# HSHV4-student_version.net
KiCad netlist of a schematic drawn in EAGLE
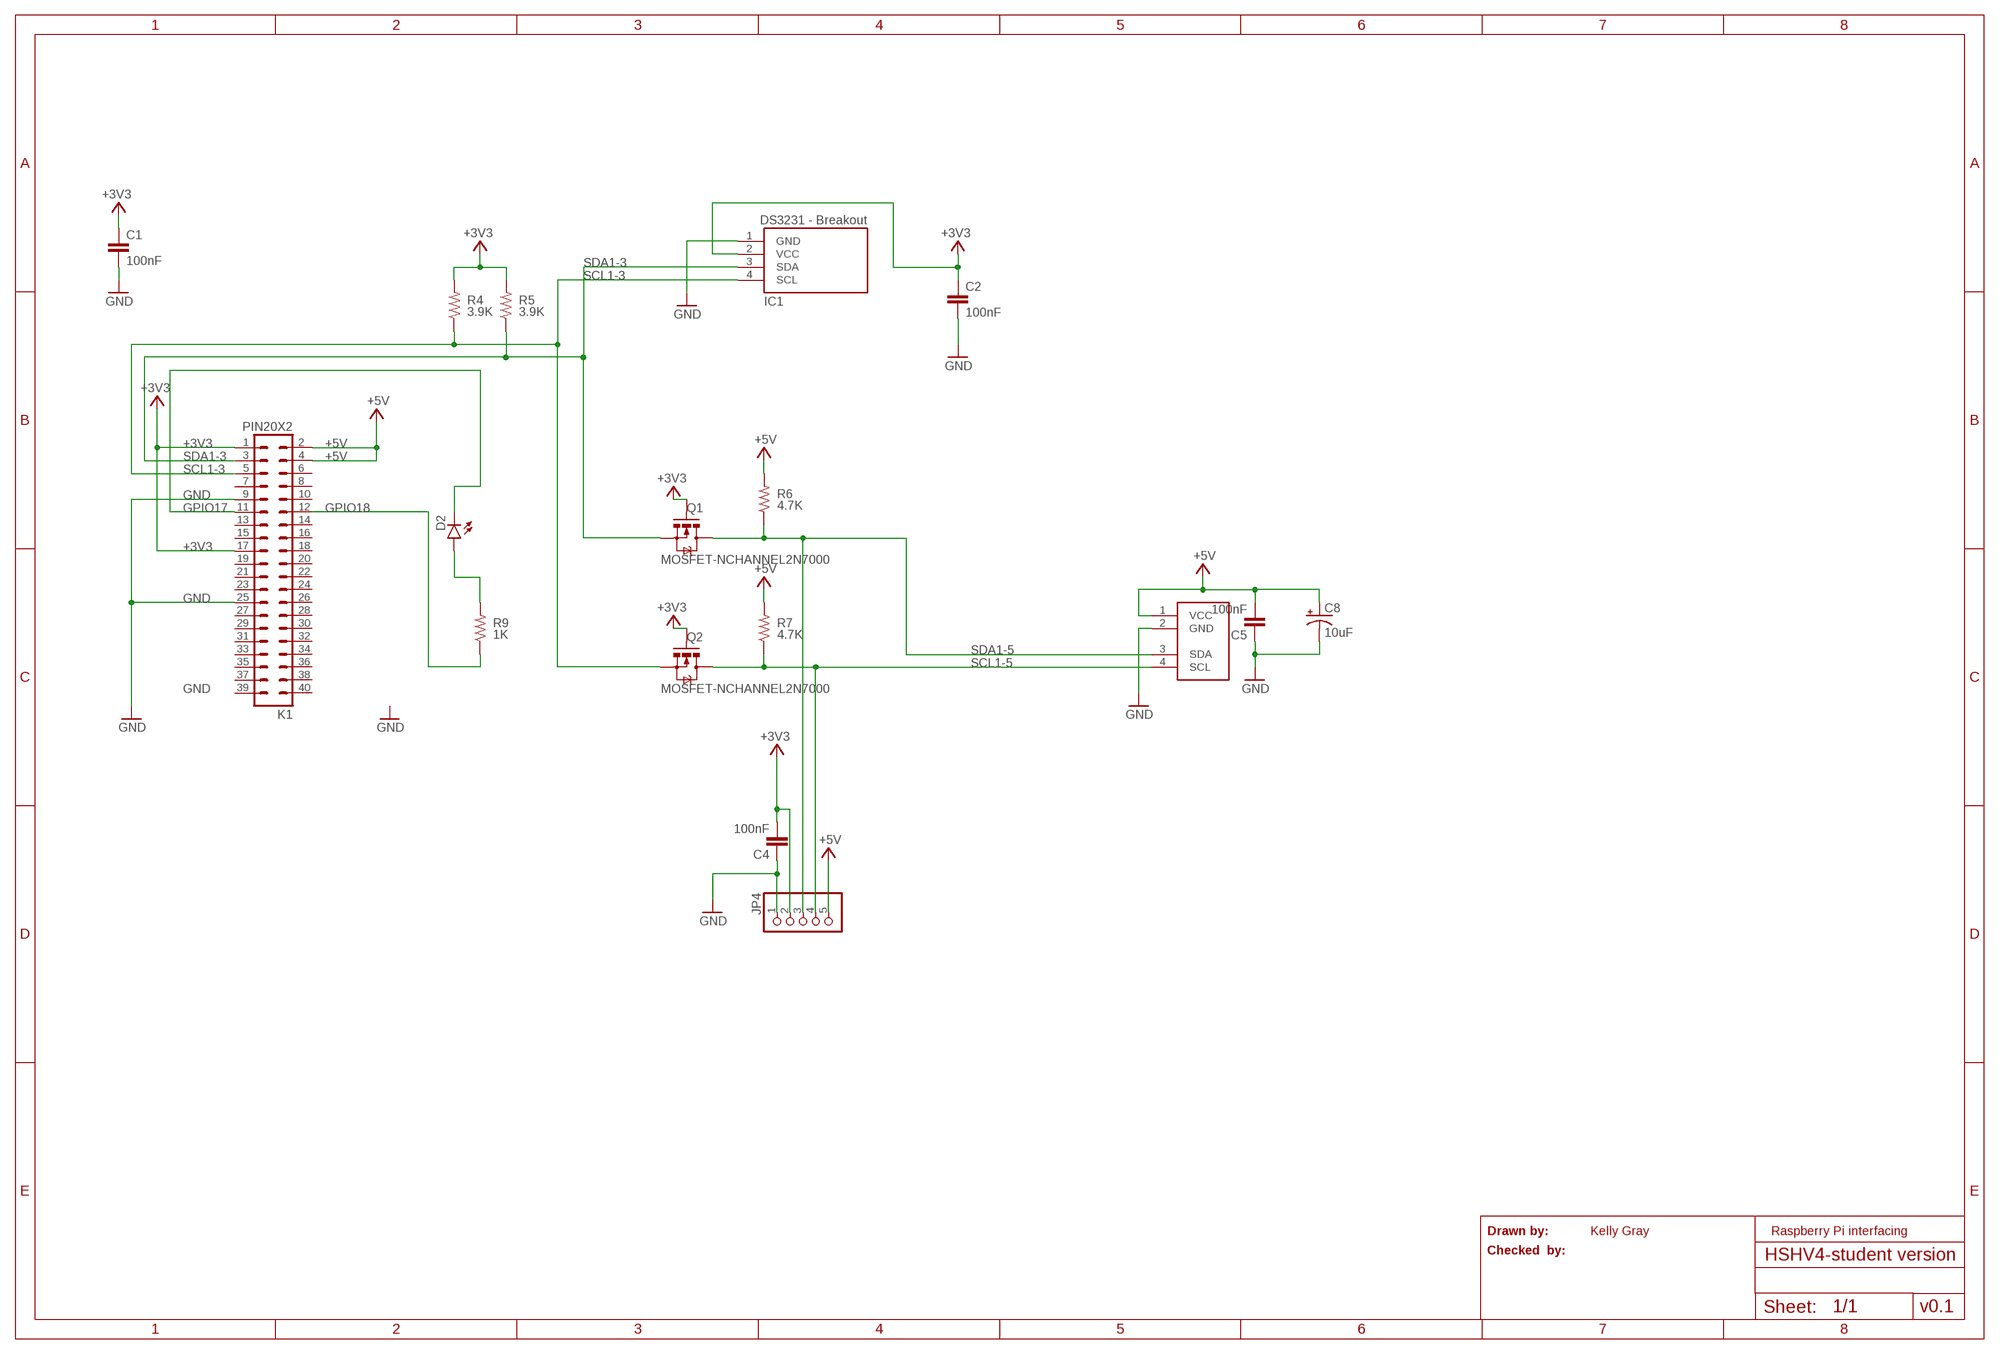
[diagram p0: schematic, sheet 1]

(export (version "E")
  (design (tool "Eeschema 10.0.6"))
  (components
    (comp (ref "C1")
      (value "100nF")
      (footprint "eagle-import:CAP-PTH-SMALL-KIT")
      (libsource (lib "eagle-import") (part "0.1UF-50V-20%(PTH)KIT-EZ"))
    )
    (comp (ref "C2")
      (value "100nF")
      (footprint "eagle-import:CAP-PTH-SMALL-KIT")
      (libsource (lib "eagle-import") (part "0.1UF-50V-20%(PTH)KIT-EZ"))
    )
    (comp (ref "C4")
      (value "100nF")
      (footprint "eagle-import:CAP-PTH-SMALL-KIT")
      (libsource (lib "eagle-import") (part "0.1UF-50V-20%(PTH)KIT-EZ"))
    )
    (comp (ref "C5")
      (value "100nF")
      (footprint "eagle-import:CAP-PTH-SMALL-KIT")
      (libsource (lib "eagle-import") (part "0.1UF-50V-20%(PTH)KIT-EZ"))
    )
    (comp (ref "C8")
      (value "10uF")
      (footprint "eagle-import:CPOL-RADIAL-10UF-25V")
      (libsource (lib "eagle-import") (part "10UF-25V-20%(PTH)"))
    )
    (comp (ref "D2")
      (value "LED-3MM-NO_SILK")
      (footprint "eagle-import:LED3MM-NS")
      (libsource (lib "eagle-import") (part "LED-3MM-NO_SILK"))
    )
    (comp (ref "IC1")
      (value "DS3231")
      (footprint "eagle-import:8PTH")
      (libsource (lib "eagle-import") (part "DS3231"))
    )
    (comp (ref "JP4")
      (value "PINHD-1X5")
      (footprint "eagle-import:1X05")
      (libsource (lib "eagle-import") (part "PINHD-1X5"))
    )
    (comp (ref "K1")
      (value "PIN20X2")
      (footprint "eagle-import:PIN_20X2")
      (libsource (lib "eagle-import") (part "PIN20X2"))
    )
    (comp (ref "Q1")
      (value "MOSFET-NCHANNEL2N7000")
      (footprint "eagle-import:TO-92")
      (libsource (lib "eagle-import") (part "MOSFET-NCHANNEL2N7000"))
    )
    (comp (ref "Q2")
      (value "MOSFET-NCHANNEL2N7000")
      (footprint "eagle-import:TO-92")
      (libsource (lib "eagle-import") (part "MOSFET-NCHANNEL2N7000"))
    )
    (comp (ref "R4")
      (value "3.9K")
      (footprint "eagle-import:AXIAL-0.3")
      (fields (field (name "TOLERANCE") "5%"))
      (libsource (lib "eagle-import") (part "1KOHM-1/4W-1%(PTH)"))
    )
    (comp (ref "R5")
      (value "3.9K")
      (footprint "eagle-import:AXIAL-0.3")
      (fields (field (name "TOLERANCE") "5%"))
      (libsource (lib "eagle-import") (part "1KOHM-1/4W-1%(PTH)"))
    )
    (comp (ref "R6")
      (value "4.7K")
      (footprint "eagle-import:AXIAL-0.3")
      (fields (field (name "TOLERANCE") "5%"))
      (libsource (lib "eagle-import") (part "1KOHM-1/4W-1%(PTH)"))
    )
    (comp (ref "R7")
      (value "4.7K")
      (footprint "eagle-import:AXIAL-0.3")
      (fields (field (name "TOLERANCE") "5%"))
      (libsource (lib "eagle-import") (part "1KOHM-1/4W-1%(PTH)"))
    )
    (comp (ref "R9")
      (value "1K")
      (footprint "eagle-import:AXIAL-0.3")
      (fields (field (name "TOLERANCE") "5%"))
      (libsource (lib "eagle-import") (part "1KOHM-1/4W-1%(PTH)"))
    )
    (comp (ref "U$1")
      (value "PCF8591")
      (footprint "eagle-import:1X04")
      (libsource (lib "eagle-import") (part "PCF8591"))
    )
  )
  (nets
    (net (code "1") (name "+3V3") (class "Default")
      (node (ref "C1") (pin "1") (pinfunction "1_1") (pintype "passive"))
      (node (ref "C2") (pin "1") (pinfunction "1_1") (pintype "passive"))
      (node (ref "C4") (pin "2") (pinfunction "2_2") (pintype "passive"))
      (node (ref "IC1") (pin "2") (pinfunction "VCC_2") (pintype "power_in"))
      (node (ref "JP4") (pin "2") (pinfunction "2_2") (pintype "passive"))
      (node (ref "K1") (pin "1") (pinfunction "1_1") (pintype "passive"))
      (node (ref "K1") (pin "17") (pinfunction "17_17") (pintype "passive"))
      (node (ref "Q1") (pin "2") (pinfunction "G_2") (pintype "passive"))
      (node (ref "Q2") (pin "2") (pinfunction "G_2") (pintype "passive"))
      (node (ref "R4") (pin "P$2") (pinfunction "2_P$2") (pintype "passive"))
      (node (ref "R5") (pin "P$2") (pinfunction "2_P$2") (pintype "passive"))
    )
    (net (code "2") (name "+5V") (class "Default")
      (node (ref "C5") (pin "2") (pinfunction "2_2") (pintype "passive"))
      (node (ref "C8") (pin "1") (pinfunction "+_1") (pintype "passive"))
      (node (ref "JP4") (pin "5") (pinfunction "5_5") (pintype "passive"))
      (node (ref "K1") (pin "2") (pinfunction "2_2") (pintype "passive"))
      (node (ref "K1") (pin "4") (pinfunction "4_4") (pintype "passive"))
      (node (ref "R6") (pin "P$2") (pinfunction "2_P$2") (pintype "passive"))
      (node (ref "R7") (pin "P$2") (pinfunction "2_P$2") (pintype "passive"))
      (node (ref "U$1") (pin "1") (pinfunction "VCC_1") (pintype "bidirectional"))
    )
    (net (code "3") (name "/GPIO17") (class "Default")
      (node (ref "D2") (pin "K") (pinfunction "C_K") (pintype "passive"))
      (node (ref "K1") (pin "11") (pinfunction "11_11") (pintype "passive"))
    )
    (net (code "4") (name "/GPIO18") (class "Default")
      (node (ref "K1") (pin "12") (pinfunction "12_12") (pintype "passive"))
      (node (ref "R9") (pin "P$1") (pinfunction "1_P$1") (pintype "passive"))
    )
    (net (code "5") (name "/SCL1-3") (class "Default")
      (node (ref "IC1") (pin "4") (pinfunction "SCL_4") (pintype "bidirectional"))
      (node (ref "K1") (pin "5") (pinfunction "5_5") (pintype "passive"))
      (node (ref "Q2") (pin "1") (pinfunction "S_1") (pintype "passive"))
      (node (ref "R4") (pin "P$1") (pinfunction "1_P$1") (pintype "passive"))
    )
    (net (code "6") (name "/SCL1-5") (class "Default")
      (node (ref "JP4") (pin "4") (pinfunction "4_4") (pintype "passive"))
      (node (ref "Q2") (pin "3") (pinfunction "D_3") (pintype "passive"))
      (node (ref "R7") (pin "P$1") (pinfunction "1_P$1") (pintype "passive"))
      (node (ref "U$1") (pin "4") (pinfunction "SCL_4") (pintype "bidirectional"))
    )
    (net (code "7") (name "/SDA1-3") (class "Default")
      (node (ref "IC1") (pin "3") (pinfunction "SDA_3") (pintype "bidirectional"))
      (node (ref "K1") (pin "3") (pinfunction "3_3") (pintype "passive"))
      (node (ref "Q1") (pin "1") (pinfunction "S_1") (pintype "passive"))
      (node (ref "R5") (pin "P$1") (pinfunction "1_P$1") (pintype "passive"))
    )
    (net (code "8") (name "/SDA1-5") (class "Default")
      (node (ref "JP4") (pin "3") (pinfunction "3_3") (pintype "passive"))
      (node (ref "Q1") (pin "3") (pinfunction "D_3") (pintype "passive"))
      (node (ref "R6") (pin "P$1") (pinfunction "1_P$1") (pintype "passive"))
      (node (ref "U$1") (pin "3") (pinfunction "SDA_3") (pintype "bidirectional"))
    )
    (net (code "9") (name "GND") (class "Default")
      (node (ref "C1") (pin "2") (pinfunction "2_2") (pintype "passive"))
      (node (ref "C2") (pin "2") (pinfunction "2_2") (pintype "passive"))
      (node (ref "C4") (pin "1") (pinfunction "1_1") (pintype "passive"))
      (node (ref "C5") (pin "1") (pinfunction "1_1") (pintype "passive"))
      (node (ref "C8") (pin "2") (pinfunction "-_2") (pintype "passive"))
      (node (ref "IC1") (pin "1") (pinfunction "GND_1") (pintype "power_in"))
      (node (ref "JP4") (pin "1") (pinfunction "1_1") (pintype "passive"))
      (node (ref "K1") (pin "25") (pinfunction "25_25") (pintype "passive"))
      (node (ref "K1") (pin "9") (pinfunction "9_9") (pintype "passive"))
      (node (ref "U$1") (pin "2") (pinfunction "GND_2") (pintype "bidirectional"))
    )
    (net (code "10") (name "Net-(R9-2)") (class "Default")
      (node (ref "D2") (pin "A") (pinfunction "A_A") (pintype "passive"))
      (node (ref "R9") (pin "P$2") (pinfunction "2_P$2") (pintype "passive"))
    )
    (net (code "11") (name "unconnected-(K1-Pad6)") (class "Default")
      (node (ref "K1") (pin "6") (pinfunction "6_6") (pintype "passive"))
    )
    (net (code "12") (name "unconnected-(K1-Pad7)") (class "Default")
      (node (ref "K1") (pin "7") (pinfunction "7_7") (pintype "passive"))
    )
    (net (code "13") (name "unconnected-(K1-Pad8)") (class "Default")
      (node (ref "K1") (pin "8") (pinfunction "8_8") (pintype "passive"))
    )
    (net (code "14") (name "unconnected-(K1-Pad10)") (class "Default")
      (node (ref "K1") (pin "10") (pinfunction "10_10") (pintype "passive"))
    )
    (net (code "15") (name "unconnected-(K1-Pad13)") (class "Default")
      (node (ref "K1") (pin "13") (pinfunction "13_13") (pintype "passive"))
    )
    (net (code "16") (name "unconnected-(K1-Pad14)") (class "Default")
      (node (ref "K1") (pin "14") (pinfunction "14_14") (pintype "passive"))
    )
    (net (code "17") (name "unconnected-(K1-Pad15)") (class "Default")
      (node (ref "K1") (pin "15") (pinfunction "15_15") (pintype "passive"))
    )
    (net (code "18") (name "unconnected-(K1-Pad16)") (class "Default")
      (node (ref "K1") (pin "16") (pinfunction "16_16") (pintype "passive"))
    )
    (net (code "19") (name "unconnected-(K1-Pad18)") (class "Default")
      (node (ref "K1") (pin "18") (pinfunction "18_18") (pintype "passive"))
    )
    (net (code "20") (name "unconnected-(K1-Pad19)") (class "Default")
      (node (ref "K1") (pin "19") (pinfunction "19_19") (pintype "passive"))
    )
    (net (code "21") (name "unconnected-(K1-Pad20)") (class "Default")
      (node (ref "K1") (pin "20") (pinfunction "20_20") (pintype "passive"))
    )
    (net (code "22") (name "unconnected-(K1-Pad21)") (class "Default")
      (node (ref "K1") (pin "21") (pinfunction "21_21") (pintype "passive"))
    )
    (net (code "23") (name "unconnected-(K1-Pad22)") (class "Default")
      (node (ref "K1") (pin "22") (pinfunction "22_22") (pintype "passive"))
    )
    (net (code "24") (name "unconnected-(K1-Pad23)") (class "Default")
      (node (ref "K1") (pin "23") (pinfunction "23_23") (pintype "passive"))
    )
    (net (code "25") (name "unconnected-(K1-Pad24)") (class "Default")
      (node (ref "K1") (pin "24") (pinfunction "24_24") (pintype "passive"))
    )
    (net (code "26") (name "unconnected-(K1-Pad26)") (class "Default")
      (node (ref "K1") (pin "26") (pinfunction "26_26") (pintype "passive"))
    )
    (net (code "27") (name "unconnected-(K1-Pad27)") (class "Default")
      (node (ref "K1") (pin "27") (pinfunction "27_27") (pintype "passive"))
    )
    (net (code "28") (name "unconnected-(K1-Pad28)") (class "Default")
      (node (ref "K1") (pin "28") (pinfunction "28_28") (pintype "passive"))
    )
    (net (code "29") (name "unconnected-(K1-Pad29)") (class "Default")
      (node (ref "K1") (pin "29") (pinfunction "29_29") (pintype "passive"))
    )
    (net (code "30") (name "unconnected-(K1-Pad30)") (class "Default")
      (node (ref "K1") (pin "30") (pinfunction "30_30") (pintype "passive"))
    )
    (net (code "31") (name "unconnected-(K1-Pad31)") (class "Default")
      (node (ref "K1") (pin "31") (pinfunction "31_31") (pintype "passive"))
    )
    (net (code "32") (name "unconnected-(K1-Pad32)") (class "Default")
      (node (ref "K1") (pin "32") (pinfunction "32_32") (pintype "passive"))
    )
    (net (code "33") (name "unconnected-(K1-Pad33)") (class "Default")
      (node (ref "K1") (pin "33") (pinfunction "33_33") (pintype "passive"))
    )
    (net (code "34") (name "unconnected-(K1-Pad34)") (class "Default")
      (node (ref "K1") (pin "34") (pinfunction "34_34") (pintype "passive"))
    )
    (net (code "35") (name "unconnected-(K1-Pad35)") (class "Default")
      (node (ref "K1") (pin "35") (pinfunction "35_35") (pintype "passive"))
    )
    (net (code "36") (name "unconnected-(K1-Pad36)") (class "Default")
      (node (ref "K1") (pin "36") (pinfunction "36_36") (pintype "passive"))
    )
    (net (code "37") (name "unconnected-(K1-Pad37)") (class "Default")
      (node (ref "K1") (pin "37") (pinfunction "37_37") (pintype "passive"))
    )
    (net (code "38") (name "unconnected-(K1-Pad38)") (class "Default")
      (node (ref "K1") (pin "38") (pinfunction "38_38") (pintype "passive"))
    )
    (net (code "39") (name "unconnected-(K1-Pad39)") (class "Default")
      (node (ref "K1") (pin "39") (pinfunction "39_39") (pintype "passive"))
    )
    (net (code "40") (name "unconnected-(K1-Pad40)") (class "Default")
      (node (ref "K1") (pin "40") (pinfunction "40_40") (pintype "passive"))
    )
  )
)
